# Externals.net
KiCad netlist of a schematic drawn in Altium Designer
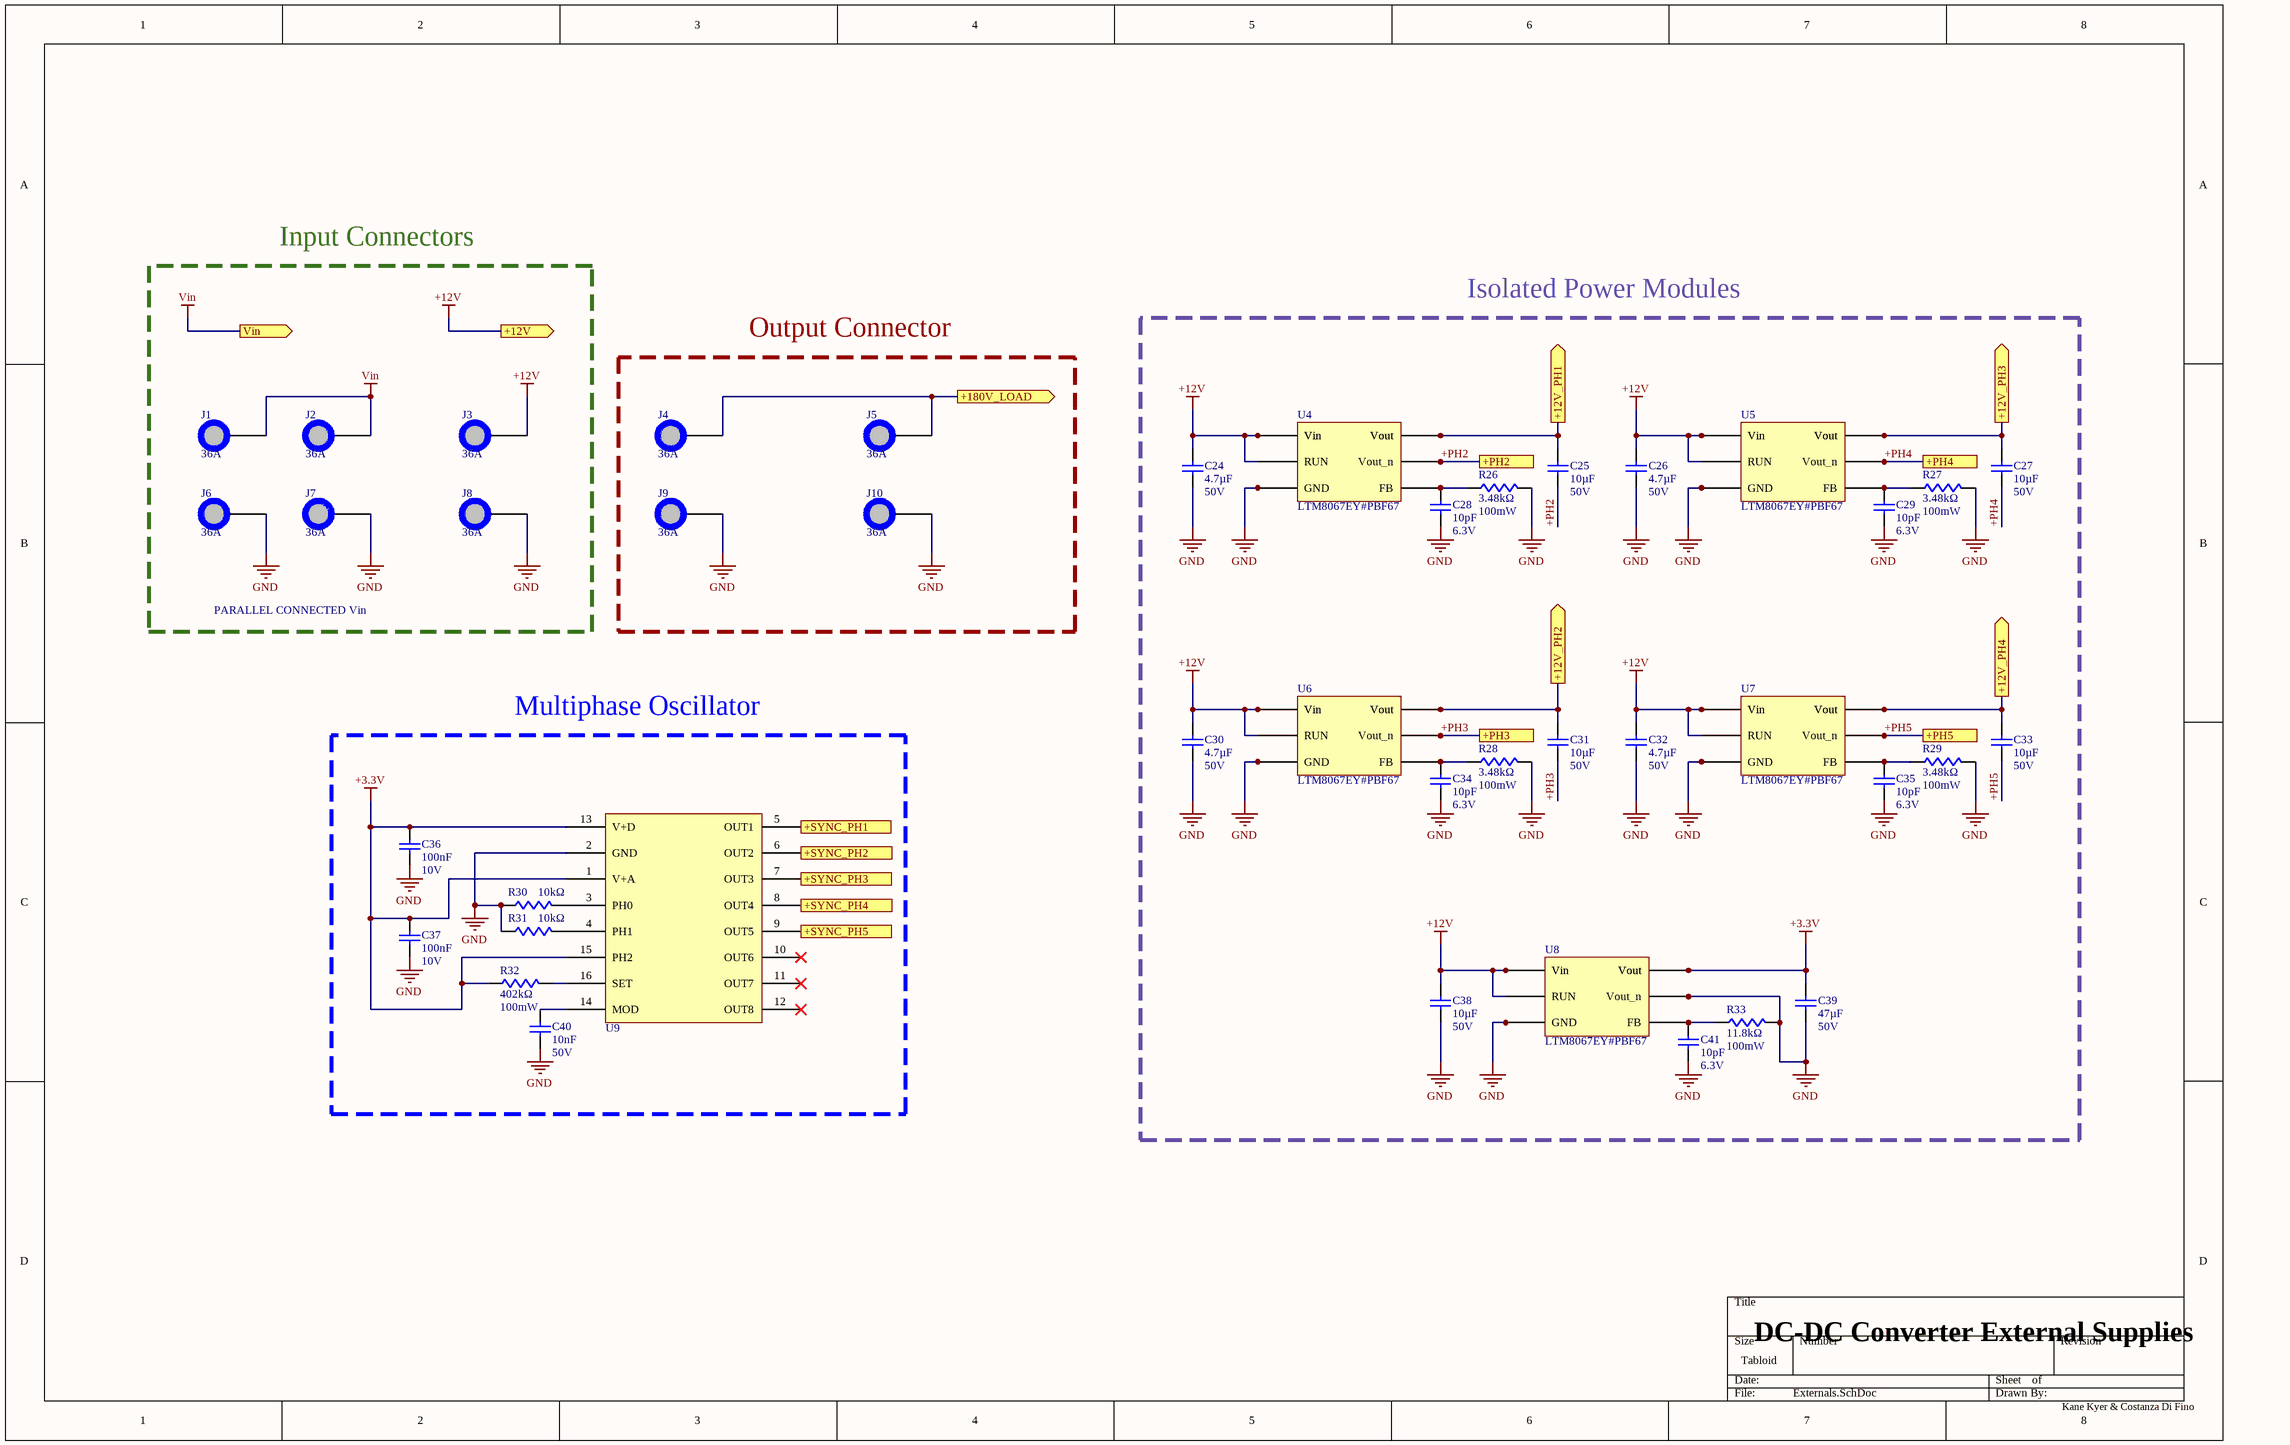
[diagram p0: Externals.SchDoc]

(export (version "E")
  (design (tool "Eeschema 10.0.6"))
  (components
    (comp (ref "C24")
      (value "4.7µF")
      (footprint "C_1206")
      (fields
        (field (name "MANUFACTURER") "Cal-Chip Electronics")
        (field (name "MANUFACTURER PART NUMBER") "GMC31X7R475K50NT")
        (field (name "VOLTAGE RATING (DC)") "50V")
      )
      (libsource (lib "library") (part "GMC31X7R475K50NT"))
    )
    (comp (ref "C25")
      (value "10µF")
      (footprint "C_1206")
      (description "50V 10uF X7R ±10% 1206 Multilayer Ceramic Capacitors MLCC - SMD/SMT ROHS")
      (fields
        (field (name "MANUFACTURER") "Samsung Electro-Mechanics")
        (field (name "MANUFACTURER PART NUMBER") "CL31B106KBHNNNE")
        (field (name "VOLTAGE RATING") "50V")
      )
      (libsource (lib "library") (part "CL31B106KBHNNNE"))
    )
    (comp (ref "C26")
      (value "4.7µF")
      (footprint "C_1206")
      (fields
        (field (name "MANUFACTURER") "Cal-Chip Electronics")
        (field (name "MANUFACTURER PART NUMBER") "GMC31X7R475K50NT")
        (field (name "VOLTAGE RATING (DC)") "50V")
      )
      (libsource (lib "library") (part "GMC31X7R475K50NT"))
    )
    (comp (ref "C27")
      (value "10µF")
      (footprint "C_1206")
      (description "50V 10uF X7R ±10% 1206 Multilayer Ceramic Capacitors MLCC - SMD/SMT ROHS")
      (fields
        (field (name "MANUFACTURER") "Samsung Electro-Mechanics")
        (field (name "MANUFACTURER PART NUMBER") "CL31B106KBHNNNE")
        (field (name "VOLTAGE RATING") "50V")
      )
      (libsource (lib "library") (part "CL31B106KBHNNNE"))
    )
    (comp (ref "C28")
      (value "10pF")
      (footprint "C_0402")
      (description "0402 10 pF 6.3 V ±10 % Tolerance C0G/NP0 SMT Multilayer Ceramic Capacitor")
      (fields
        (field (name "MANUFACTURER") "KYOCERA AVX")
        (field (name "MANUFACTURER PART NUMBER") "04026A100KAT2A")
        (field (name "VOLTAGE RATING") "6.3V")
      )
      (libsource (lib "library") (part "04026A100KAT2A"))
    )
    (comp (ref "C29")
      (value "10pF")
      (footprint "C_0402")
      (description "0402 10 pF 6.3 V ±10 % Tolerance C0G/NP0 SMT Multilayer Ceramic Capacitor")
      (fields
        (field (name "MANUFACTURER") "KYOCERA AVX")
        (field (name "MANUFACTURER PART NUMBER") "04026A100KAT2A")
        (field (name "VOLTAGE RATING") "6.3V")
      )
      (libsource (lib "library") (part "04026A100KAT2A"))
    )
    (comp (ref "C30")
      (value "4.7µF")
      (footprint "C_1206")
      (fields
        (field (name "MANUFACTURER") "Cal-Chip Electronics")
        (field (name "MANUFACTURER PART NUMBER") "GMC31X7R475K50NT")
        (field (name "VOLTAGE RATING (DC)") "50V")
      )
      (libsource (lib "library") (part "GMC31X7R475K50NT"))
    )
    (comp (ref "C31")
      (value "10µF")
      (footprint "C_1206")
      (description "50V 10uF X7R ±10% 1206 Multilayer Ceramic Capacitors MLCC - SMD/SMT ROHS")
      (fields
        (field (name "MANUFACTURER") "Samsung Electro-Mechanics")
        (field (name "MANUFACTURER PART NUMBER") "CL31B106KBHNNNE")
        (field (name "VOLTAGE RATING") "50V")
      )
      (libsource (lib "library") (part "CL31B106KBHNNNE"))
    )
    (comp (ref "C32")
      (value "4.7µF")
      (footprint "C_1206")
      (fields
        (field (name "MANUFACTURER") "Cal-Chip Electronics")
        (field (name "MANUFACTURER PART NUMBER") "GMC31X7R475K50NT")
        (field (name "VOLTAGE RATING (DC)") "50V")
      )
      (libsource (lib "library") (part "GMC31X7R475K50NT"))
    )
    (comp (ref "C33")
      (value "10µF")
      (footprint "C_1206")
      (description "50V 10uF X7R ±10% 1206 Multilayer Ceramic Capacitors MLCC - SMD/SMT ROHS")
      (fields
        (field (name "MANUFACTURER") "Samsung Electro-Mechanics")
        (field (name "MANUFACTURER PART NUMBER") "CL31B106KBHNNNE")
        (field (name "VOLTAGE RATING") "50V")
      )
      (libsource (lib "library") (part "CL31B106KBHNNNE"))
    )
    (comp (ref "C34")
      (value "10pF")
      (footprint "C_0402")
      (description "0402 10 pF 6.3 V ±10 % Tolerance C0G/NP0 SMT Multilayer Ceramic Capacitor")
      (fields
        (field (name "MANUFACTURER") "KYOCERA AVX")
        (field (name "MANUFACTURER PART NUMBER") "04026A100KAT2A")
        (field (name "VOLTAGE RATING") "6.3V")
      )
      (libsource (lib "library") (part "04026A100KAT2A"))
    )
    (comp (ref "C35")
      (value "10pF")
      (footprint "C_0402")
      (description "0402 10 pF 6.3 V ±10 % Tolerance C0G/NP0 SMT Multilayer Ceramic Capacitor")
      (fields
        (field (name "MANUFACTURER") "KYOCERA AVX")
        (field (name "MANUFACTURER PART NUMBER") "04026A100KAT2A")
        (field (name "VOLTAGE RATING") "6.3V")
      )
      (libsource (lib "library") (part "04026A100KAT2A"))
    )
    (comp (ref "C36")
      (value "100nF")
      (footprint "C_0402")
      (description "10V 100nF X7R ±10% 0402 Multilayer Ceramic Capacitors MLCC - SMD/SMT ROHS")
      (fields
        (field (name "MANUFACTURER") "Cal-Chip Electronics")
        (field (name "MANUFACTURER PART NUMBER") "GMC04X7R104K10NT")
        (field (name "VOLTAGE RATING (DC)") "10V")
      )
      (libsource (lib "library") (part "GMC04X7R104K10NT"))
    )
    (comp (ref "C37")
      (value "100nF")
      (footprint "C_0402")
      (description "10V 100nF X7R ±10% 0402 Multilayer Ceramic Capacitors MLCC - SMD/SMT ROHS")
      (fields
        (field (name "MANUFACTURER") "Cal-Chip Electronics")
        (field (name "MANUFACTURER PART NUMBER") "GMC04X7R104K10NT")
        (field (name "VOLTAGE RATING (DC)") "10V")
      )
      (libsource (lib "library") (part "GMC04X7R104K10NT"))
    )
    (comp (ref "C38")
      (value "10µF")
      (footprint "C_1206")
      (description "50V 10uF X7R ±10% 1206 Multilayer Ceramic Capacitors MLCC - SMD/SMT ROHS")
      (fields
        (field (name "MANUFACTURER") "Samsung Electro-Mechanics")
        (field (name "MANUFACTURER PART NUMBER") "CL31B106KBHNNNE")
        (field (name "VOLTAGE RATING") "50V")
      )
      (libsource (lib "library") (part "CL31B106KBHNNNE"))
    )
    (comp (ref "C39")
      (value "47µF")
      (footprint "C_CKG57N")
      (fields
        (field (name "MANUFACTURER") "TDK")
        (field (name "MANUFACTURER PART NUMBER") "CKG57NX7R1H476M500JJ")
        (field (name "VOLTAGE RATING (DC)") "50V")
      )
      (libsource (lib "library") (part "CKG57NX7R1H476M500JJ"))
    )
    (comp (ref "C40")
      (value "10nF")
      (footprint "C_0603")
      (description "Capacitor, Multilayer, Ceramic, 50V, 10%, X7R, 15% Tc, 0.01Uf, Surface Mount, 0603")
      (fields
        (field (name "MANUFACTURER") "KEMET")
        (field (name "MANUFACTURER PART NUMBER") "C0603C103K5RACTU")
        (field (name "VOLTAGE RATING") "50V")
      )
      (libsource (lib "library") (part "C0603C103K5RACTU"))
    )
    (comp (ref "C41")
      (value "10pF")
      (footprint "C_0402")
      (description "0402 10 pF 6.3 V ±10 % Tolerance C0G/NP0 SMT Multilayer Ceramic Capacitor")
      (fields
        (field (name "MANUFACTURER") "KYOCERA AVX")
        (field (name "MANUFACTURER PART NUMBER") "04026A100KAT2A")
        (field (name "VOLTAGE RATING") "6.3V")
      )
      (libsource (lib "library") (part "04026A100KAT2A"))
    )
    (comp (ref "J1")
      (value "SMTSO-116-8ET")
      (footprint "PEM")
      (description "ReelFast Surface Mount Nuts and Spacers/Standoffs -br Type SMTSO - Unified")
      (fields (field (name "MANUFACTURER") "PennEngineering") (field (name "CURRENT RATING") "36A"))
      (libsource (lib "library") (part "SMTSO-116-8ET"))
    )
    (comp (ref "J2")
      (value "SMTSO-116-8ET")
      (footprint "PEM")
      (description "ReelFast Surface Mount Nuts and Spacers/Standoffs -br Type SMTSO - Unified")
      (fields (field (name "MANUFACTURER") "PennEngineering") (field (name "CURRENT RATING") "36A"))
      (libsource (lib "library") (part "SMTSO-116-8ET"))
    )
    (comp (ref "J3")
      (value "SMTSO-116-8ET")
      (footprint "PEM")
      (description "ReelFast Surface Mount Nuts and Spacers/Standoffs -br Type SMTSO - Unified")
      (fields (field (name "MANUFACTURER") "PennEngineering") (field (name "CURRENT RATING") "36A"))
      (libsource (lib "library") (part "SMTSO-116-8ET"))
    )
    (comp (ref "J4")
      (value "SMTSO-116-8ET")
      (footprint "PEM")
      (description "ReelFast Surface Mount Nuts and Spacers/Standoffs -br Type SMTSO - Unified")
      (fields (field (name "MANUFACTURER") "PennEngineering") (field (name "CURRENT RATING") "36A"))
      (libsource (lib "library") (part "SMTSO-116-8ET"))
    )
    (comp (ref "J5")
      (value "SMTSO-116-8ET")
      (footprint "PEM")
      (description "ReelFast Surface Mount Nuts and Spacers/Standoffs -br Type SMTSO - Unified")
      (fields (field (name "MANUFACTURER") "PennEngineering") (field (name "CURRENT RATING") "36A"))
      (libsource (lib "library") (part "SMTSO-116-8ET"))
    )
    (comp (ref "J6")
      (value "SMTSO-116-8ET")
      (footprint "PEM")
      (description "ReelFast Surface Mount Nuts and Spacers/Standoffs -br Type SMTSO - Unified")
      (fields (field (name "MANUFACTURER") "PennEngineering") (field (name "CURRENT RATING") "36A"))
      (libsource (lib "library") (part "SMTSO-116-8ET"))
    )
    (comp (ref "J7")
      (value "SMTSO-116-8ET")
      (footprint "PEM")
      (description "ReelFast Surface Mount Nuts and Spacers/Standoffs -br Type SMTSO - Unified")
      (fields (field (name "MANUFACTURER") "PennEngineering") (field (name "CURRENT RATING") "36A"))
      (libsource (lib "library") (part "SMTSO-116-8ET"))
    )
    (comp (ref "J8")
      (value "SMTSO-116-8ET")
      (footprint "PEM")
      (description "ReelFast Surface Mount Nuts and Spacers/Standoffs -br Type SMTSO - Unified")
      (fields (field (name "MANUFACTURER") "PennEngineering") (field (name "CURRENT RATING") "36A"))
      (libsource (lib "library") (part "SMTSO-116-8ET"))
    )
    (comp (ref "J9")
      (value "SMTSO-116-8ET")
      (footprint "PEM")
      (description "ReelFast Surface Mount Nuts and Spacers/Standoffs -br Type SMTSO - Unified")
      (fields (field (name "MANUFACTURER") "PennEngineering") (field (name "CURRENT RATING") "36A"))
      (libsource (lib "library") (part "SMTSO-116-8ET"))
    )
    (comp (ref "J10")
      (value "SMTSO-116-8ET")
      (footprint "PEM")
      (description "ReelFast Surface Mount Nuts and Spacers/Standoffs -br Type SMTSO - Unified")
      (fields (field (name "MANUFACTURER") "PennEngineering") (field (name "CURRENT RATING") "36A"))
      (libsource (lib "library") (part "SMTSO-116-8ET"))
    )
    (comp (ref "R26")
      (value "3.48kΩ")
      (footprint "R_0603")
      (description "Fixed Resistor, Metal Glaze/thick Film, 0.1W, 3480ohm, 75V, 1% +/-Tol, Surface Mount, 0603")
      (fields
        (field (name "MANUFACTURER") "Cal-Chip Electronics")
        (field (name "MANUFACTURER PART NUMBER") "RM06F3481CT")
        (field (name "POWER DISSIPATION") "100mW")
      )
      (libsource (lib "library") (part "RM06F3481CT"))
    )
    (comp (ref "R27")
      (value "3.48kΩ")
      (footprint "R_0603")
      (description "Fixed Resistor, Metal Glaze/thick Film, 0.1W, 3480ohm, 75V, 1% +/-Tol, Surface Mount, 0603")
      (fields
        (field (name "MANUFACTURER") "Cal-Chip Electronics")
        (field (name "MANUFACTURER PART NUMBER") "RM06F3481CT")
        (field (name "POWER DISSIPATION") "100mW")
      )
      (libsource (lib "library") (part "RM06F3481CT"))
    )
    (comp (ref "R28")
      (value "3.48kΩ")
      (footprint "R_0603")
      (description "Fixed Resistor, Metal Glaze/thick Film, 0.1W, 3480ohm, 75V, 1% +/-Tol, Surface Mount, 0603")
      (fields
        (field (name "MANUFACTURER") "Cal-Chip Electronics")
        (field (name "MANUFACTURER PART NUMBER") "RM06F3481CT")
        (field (name "POWER DISSIPATION") "100mW")
      )
      (libsource (lib "library") (part "RM06F3481CT"))
    )
    (comp (ref "R29")
      (value "3.48kΩ")
      (footprint "R_0603")
      (description "Fixed Resistor, Metal Glaze/thick Film, 0.1W, 3480ohm, 75V, 1% +/-Tol, Surface Mount, 0603")
      (fields
        (field (name "MANUFACTURER") "Cal-Chip Electronics")
        (field (name "MANUFACTURER PART NUMBER") "RM06F3481CT")
        (field (name "POWER DISSIPATION") "100mW")
      )
      (libsource (lib "library") (part "RM06F3481CT"))
    )
    (comp (ref "R30")
      (value "10kΩ")
      (footprint "R_0402")
      (description "Fixed Resistor, Metal Glaze/thick Film, 0.0625W, 10000ohm, 50V, 1% +/-Tol, Surface Mount, 0402")
      (fields
        (field (name "MANUFACTURER") "Cal-Chip Electronics")
        (field (name "MANUFACTURER PART NUMBER") "RM04F1002CT")
      )
      (libsource (lib "library") (part "RM04F1002CT"))
    )
    (comp (ref "R31")
      (value "10kΩ")
      (footprint "R_0402")
      (description "Fixed Resistor, Metal Glaze/thick Film, 0.0625W, 10000ohm, 50V, 1% +/-Tol, Surface Mount, 0402")
      (fields
        (field (name "MANUFACTURER") "Cal-Chip Electronics")
        (field (name "MANUFACTURER PART NUMBER") "RM04F1002CT")
      )
      (libsource (lib "library") (part "RM04F1002CT"))
    )
    (comp (ref "R32")
      (value "402kΩ")
      (footprint "R_0603")
      (description "100mW Thick Film Resistors 75V ±100ppm/℃ ±1% 402kΩ 0603 Chip Resistor - Surface Mount ROHS")
      (fields
        (field (name "MANUFACTURER") "Yageo Group")
        (field (name "MANUFACTURER PART NUMBER") "RC0603FR-07402KL")
        (field (name "POWER DISSIPATION") "100mW")
      )
      (libsource (lib "library") (part "RC0603FR-07402KL"))
    )
    (comp (ref "R33")
      (value "11.8kΩ")
      (footprint "R_0603")
      (description "Res Thick Film 0603 11.8K Ohm 1% 0.1W(1/10W) ±100ppm/C Pad SMD Automotive T/R")
      (fields
        (field (name "MANUFACTURER") "KOA Speer")
        (field (name "MANUFACTURER PART NUMBER") "RK73H1JTTD1182F")
        (field (name "POWER DISSIPATION") "100mW")
      )
      (libsource (lib "library") (part "RK73H1JTTD1182F"))
    )
    (comp (ref "U4")
      (value "LTM8067EY#PBF")
      (footprint "LTM8067")
      (description "Module DC-DC 1-OUT 2.5V to 24V 0.45A 2.5W 38-Pin BGA Tray")
      (fields
        (field (name "MANUFACTURER") "Analog Devices")
        (field (name "MANUFACTURER PART NUMBER") "LTM8067EY#PBF67")
      )
      (libsource (lib "library") (part "LTM8067EY#PBF"))
    )
    (comp (ref "U5")
      (value "LTM8067EY#PBF")
      (footprint "LTM8067")
      (description "Module DC-DC 1-OUT 2.5V to 24V 0.45A 2.5W 38-Pin BGA Tray")
      (fields
        (field (name "MANUFACTURER") "Analog Devices")
        (field (name "MANUFACTURER PART NUMBER") "LTM8067EY#PBF67")
      )
      (libsource (lib "library") (part "LTM8067EY#PBF"))
    )
    (comp (ref "U6")
      (value "LTM8067EY#PBF")
      (footprint "LTM8067")
      (description "Module DC-DC 1-OUT 2.5V to 24V 0.45A 2.5W 38-Pin BGA Tray")
      (fields
        (field (name "MANUFACTURER") "Analog Devices")
        (field (name "MANUFACTURER PART NUMBER") "LTM8067EY#PBF67")
      )
      (libsource (lib "library") (part "LTM8067EY#PBF"))
    )
    (comp (ref "U7")
      (value "LTM8067EY#PBF")
      (footprint "LTM8067")
      (description "Module DC-DC 1-OUT 2.5V to 24V 0.45A 2.5W 38-Pin BGA Tray")
      (fields
        (field (name "MANUFACTURER") "Analog Devices")
        (field (name "MANUFACTURER PART NUMBER") "LTM8067EY#PBF67")
      )
      (libsource (lib "library") (part "LTM8067EY#PBF"))
    )
    (comp (ref "U8")
      (value "LTM8067EY#PBF")
      (footprint "LTM8067")
      (description "Module DC-DC 1-OUT 2.5V to 24V 0.45A 2.5W 38-Pin BGA Tray")
      (fields
        (field (name "MANUFACTURER") "Analog Devices")
        (field (name "MANUFACTURER PART NUMBER") "LTM8067EY#PBF67")
      )
      (libsource (lib "library") (part "LTM8067EY#PBF"))
    )
    (comp (ref "U9")
      (value "LTC6909HMS#TRPBF")
      (footprint "LTC6909")
      (description "1 to 8 Output, Multiphase Silicon Oscillator with Spread Spectrum Modulation")
      (fields (field (name "MANUFACTURER") "Analog Devices"))
      (libsource (lib "library") (part "LTC6909HMS#TRPBF"))
    )
  )
  (nets
    (net (code "1") (name "+3.3V") (class "Default")
      (node (ref "C36") (pin "2") (pintype "passive"))
      (node (ref "C37") (pin "2") (pintype "passive"))
      (node (ref "C39") (pin "2") (pintype "passive"))
      (node (ref "R32") (pin "1") (pintype "passive"))
      (node (ref "U8") (pin "A6") (pinfunction "Vout_A6") (pintype "passive"))
      (node (ref "U8") (pin "A7") (pinfunction "Vout_A7") (pintype "passive"))
      (node (ref "U8") (pin "B6") (pinfunction "Vout_B6") (pintype "passive"))
      (node (ref "U8") (pin "B7") (pinfunction "Vout_B7") (pintype "passive"))
      (node (ref "U9") (pin "1") (pinfunction "V+A_1") (pintype "passive"))
      (node (ref "U9") (pin "13") (pinfunction "V+D_13") (pintype "passive"))
      (node (ref "U9") (pin "15") (pinfunction "PH2_15") (pintype "passive"))
    )
    (net (code "2") (name "+12V") (class "Default")
      (node (ref "C24") (pin "2") (pintype "passive"))
      (node (ref "C26") (pin "2") (pintype "passive"))
      (node (ref "C30") (pin "2") (pintype "passive"))
      (node (ref "C32") (pin "2") (pintype "passive"))
      (node (ref "C38") (pin "2") (pintype "passive"))
      (node (ref "J3") (pin "1") (pinfunction "1_1") (pintype "passive"))
      (node (ref "U4") (pin "F3") (pinfunction "RUN_F3") (pintype "passive"))
      (node (ref "U4") (pin "G1") (pinfunction "Vin_G1") (pintype "passive"))
      (node (ref "U4") (pin "G2") (pinfunction "Vin_G2") (pintype "passive"))
      (node (ref "U4") (pin "H1") (pinfunction "Vin_H1") (pintype "passive"))
      (node (ref "U4") (pin "H2") (pinfunction "Vin_H2") (pintype "passive"))
      (node (ref "U5") (pin "F3") (pinfunction "RUN_F3") (pintype "passive"))
      (node (ref "U5") (pin "G1") (pinfunction "Vin_G1") (pintype "passive"))
      (node (ref "U5") (pin "G2") (pinfunction "Vin_G2") (pintype "passive"))
      (node (ref "U5") (pin "H1") (pinfunction "Vin_H1") (pintype "passive"))
      (node (ref "U5") (pin "H2") (pinfunction "Vin_H2") (pintype "passive"))
      (node (ref "U6") (pin "F3") (pinfunction "RUN_F3") (pintype "passive"))
      (node (ref "U6") (pin "G1") (pinfunction "Vin_G1") (pintype "passive"))
      (node (ref "U6") (pin "G2") (pinfunction "Vin_G2") (pintype "passive"))
      (node (ref "U6") (pin "H1") (pinfunction "Vin_H1") (pintype "passive"))
      (node (ref "U6") (pin "H2") (pinfunction "Vin_H2") (pintype "passive"))
      (node (ref "U7") (pin "F3") (pinfunction "RUN_F3") (pintype "passive"))
      (node (ref "U7") (pin "G1") (pinfunction "Vin_G1") (pintype "passive"))
      (node (ref "U7") (pin "G2") (pinfunction "Vin_G2") (pintype "passive"))
      (node (ref "U7") (pin "H1") (pinfunction "Vin_H1") (pintype "passive"))
      (node (ref "U7") (pin "H2") (pinfunction "Vin_H2") (pintype "passive"))
      (node (ref "U8") (pin "F3") (pinfunction "RUN_F3") (pintype "passive"))
      (node (ref "U8") (pin "G1") (pinfunction "Vin_G1") (pintype "passive"))
      (node (ref "U8") (pin "G2") (pinfunction "Vin_G2") (pintype "passive"))
      (node (ref "U8") (pin "H1") (pinfunction "Vin_H1") (pintype "passive"))
      (node (ref "U8") (pin "H2") (pinfunction "Vin_H2") (pintype "passive"))
    )
    (net (code "3") (name "/+12V_PH1") (class "Default")
      (node (ref "C25") (pin "2") (pintype "passive"))
      (node (ref "U4") (pin "A6") (pinfunction "Vout_A6") (pintype "passive"))
      (node (ref "U4") (pin "A7") (pinfunction "Vout_A7") (pintype "passive"))
      (node (ref "U4") (pin "B6") (pinfunction "Vout_B6") (pintype "passive"))
      (node (ref "U4") (pin "B7") (pinfunction "Vout_B7") (pintype "passive"))
    )
    (net (code "4") (name "/+12V_PH2") (class "Default")
      (node (ref "C31") (pin "2") (pintype "passive"))
      (node (ref "U6") (pin "A6") (pinfunction "Vout_A6") (pintype "passive"))
      (node (ref "U6") (pin "A7") (pinfunction "Vout_A7") (pintype "passive"))
      (node (ref "U6") (pin "B6") (pinfunction "Vout_B6") (pintype "passive"))
      (node (ref "U6") (pin "B7") (pinfunction "Vout_B7") (pintype "passive"))
    )
    (net (code "5") (name "/+12V_PH3") (class "Default")
      (node (ref "C27") (pin "2") (pintype "passive"))
      (node (ref "U5") (pin "A6") (pinfunction "Vout_A6") (pintype "passive"))
      (node (ref "U5") (pin "A7") (pinfunction "Vout_A7") (pintype "passive"))
      (node (ref "U5") (pin "B6") (pinfunction "Vout_B6") (pintype "passive"))
      (node (ref "U5") (pin "B7") (pinfunction "Vout_B7") (pintype "passive"))
    )
    (net (code "6") (name "/+12V_PH4") (class "Default")
      (node (ref "C33") (pin "2") (pintype "passive"))
      (node (ref "U7") (pin "A6") (pinfunction "Vout_A6") (pintype "passive"))
      (node (ref "U7") (pin "A7") (pinfunction "Vout_A7") (pintype "passive"))
      (node (ref "U7") (pin "B6") (pinfunction "Vout_B6") (pintype "passive"))
      (node (ref "U7") (pin "B7") (pinfunction "Vout_B7") (pintype "passive"))
    )
    (net (code "7") (name "/+180V_LOAD") (class "Default")
      (node (ref "J4") (pin "1") (pinfunction "1_1") (pintype "passive"))
      (node (ref "J5") (pin "1") (pinfunction "1_1") (pintype "passive"))
    )
    (net (code "8") (name "/+PH2") (class "Default")
      (node (ref "C25") (pin "1") (pintype "passive"))
      (node (ref "U4") (pin "A1") (pinfunction "Vout_n_A1") (pintype "passive"))
      (node (ref "U4") (pin "A2") (pinfunction "Vout_n_A2") (pintype "passive"))
      (node (ref "U4") (pin "A3") (pinfunction "Vout_n_A3") (pintype "passive"))
      (node (ref "U4") (pin "A4") (pinfunction "Vout_n_A4") (pintype "passive"))
      (node (ref "U4") (pin "A5") (pinfunction "Vout_n_A5") (pintype "passive"))
      (node (ref "U4") (pin "B1") (pinfunction "Vout_n_B1") (pintype "passive"))
      (node (ref "U4") (pin "B2") (pinfunction "Vout_n_B2") (pintype "passive"))
      (node (ref "U4") (pin "B3") (pinfunction "Vout_n_B3") (pintype "passive"))
      (node (ref "U4") (pin "B4") (pinfunction "Vout_n_B4") (pintype "passive"))
      (node (ref "U4") (pin "B5") (pinfunction "Vout_n_B5") (pintype "passive"))
    )
    (net (code "9") (name "/+PH3") (class "Default")
      (node (ref "C31") (pin "1") (pintype "passive"))
      (node (ref "U6") (pin "A1") (pinfunction "Vout_n_A1") (pintype "passive"))
      (node (ref "U6") (pin "A2") (pinfunction "Vout_n_A2") (pintype "passive"))
      (node (ref "U6") (pin "A3") (pinfunction "Vout_n_A3") (pintype "passive"))
      (node (ref "U6") (pin "A4") (pinfunction "Vout_n_A4") (pintype "passive"))
      (node (ref "U6") (pin "A5") (pinfunction "Vout_n_A5") (pintype "passive"))
      (node (ref "U6") (pin "B1") (pinfunction "Vout_n_B1") (pintype "passive"))
      (node (ref "U6") (pin "B2") (pinfunction "Vout_n_B2") (pintype "passive"))
      (node (ref "U6") (pin "B3") (pinfunction "Vout_n_B3") (pintype "passive"))
      (node (ref "U6") (pin "B4") (pinfunction "Vout_n_B4") (pintype "passive"))
      (node (ref "U6") (pin "B5") (pinfunction "Vout_n_B5") (pintype "passive"))
    )
    (net (code "10") (name "/+PH4") (class "Default")
      (node (ref "C27") (pin "1") (pintype "passive"))
      (node (ref "U5") (pin "A1") (pinfunction "Vout_n_A1") (pintype "passive"))
      (node (ref "U5") (pin "A2") (pinfunction "Vout_n_A2") (pintype "passive"))
      (node (ref "U5") (pin "A3") (pinfunction "Vout_n_A3") (pintype "passive"))
      (node (ref "U5") (pin "A4") (pinfunction "Vout_n_A4") (pintype "passive"))
      (node (ref "U5") (pin "A5") (pinfunction "Vout_n_A5") (pintype "passive"))
      (node (ref "U5") (pin "B1") (pinfunction "Vout_n_B1") (pintype "passive"))
      (node (ref "U5") (pin "B2") (pinfunction "Vout_n_B2") (pintype "passive"))
      (node (ref "U5") (pin "B3") (pinfunction "Vout_n_B3") (pintype "passive"))
      (node (ref "U5") (pin "B4") (pinfunction "Vout_n_B4") (pintype "passive"))
      (node (ref "U5") (pin "B5") (pinfunction "Vout_n_B5") (pintype "passive"))
    )
    (net (code "11") (name "/+PH5") (class "Default")
      (node (ref "C33") (pin "1") (pintype "passive"))
      (node (ref "U7") (pin "A1") (pinfunction "Vout_n_A1") (pintype "passive"))
      (node (ref "U7") (pin "A2") (pinfunction "Vout_n_A2") (pintype "passive"))
      (node (ref "U7") (pin "A3") (pinfunction "Vout_n_A3") (pintype "passive"))
      (node (ref "U7") (pin "A4") (pinfunction "Vout_n_A4") (pintype "passive"))
      (node (ref "U7") (pin "A5") (pinfunction "Vout_n_A5") (pintype "passive"))
      (node (ref "U7") (pin "B1") (pinfunction "Vout_n_B1") (pintype "passive"))
      (node (ref "U7") (pin "B2") (pinfunction "Vout_n_B2") (pintype "passive"))
      (node (ref "U7") (pin "B3") (pinfunction "Vout_n_B3") (pintype "passive"))
      (node (ref "U7") (pin "B4") (pinfunction "Vout_n_B4") (pintype "passive"))
      (node (ref "U7") (pin "B5") (pinfunction "Vout_n_B5") (pintype "passive"))
    )
    (net (code "12") (name "/+SYNC_PH1") (class "Default")
      (node (ref "U9") (pin "5") (pinfunction "OUT1_5") (pintype "passive"))
    )
    (net (code "13") (name "/+SYNC_PH2") (class "Default")
      (node (ref "U9") (pin "6") (pinfunction "OUT2_6") (pintype "passive"))
    )
    (net (code "14") (name "/+SYNC_PH3") (class "Default")
      (node (ref "U9") (pin "7") (pinfunction "OUT3_7") (pintype "passive"))
    )
    (net (code "15") (name "/+SYNC_PH4") (class "Default")
      (node (ref "U9") (pin "8") (pinfunction "OUT4_8") (pintype "passive"))
    )
    (net (code "16") (name "/+SYNC_PH5") (class "Default")
      (node (ref "U9") (pin "9") (pinfunction "OUT5_9") (pintype "passive"))
    )
    (net (code "17") (name "GND") (class "Default")
      (node (ref "C24") (pin "1") (pintype "passive"))
      (node (ref "C26") (pin "1") (pintype "passive"))
      (node (ref "C28") (pin "2") (pintype "passive"))
      (node (ref "C29") (pin "2") (pintype "passive"))
      (node (ref "C30") (pin "1") (pintype "passive"))
      (node (ref "C32") (pin "1") (pintype "passive"))
      (node (ref "C34") (pin "2") (pintype "passive"))
      (node (ref "C35") (pin "2") (pintype "passive"))
      (node (ref "C36") (pin "1") (pintype "passive"))
      (node (ref "C37") (pin "1") (pintype "passive"))
      (node (ref "C38") (pin "1") (pintype "passive"))
      (node (ref "C39") (pin "1") (pintype "passive"))
      (node (ref "C40") (pin "1") (pintype "passive"))
      (node (ref "C41") (pin "2") (pintype "passive"))
      (node (ref "J10") (pin "1") (pinfunction "1_1") (pintype "passive"))
      (node (ref "J6") (pin "1") (pinfunction "1_1") (pintype "passive"))
      (node (ref "J7") (pin "1") (pinfunction "1_1") (pintype "passive"))
      (node (ref "J8") (pin "1") (pinfunction "1_1") (pintype "passive"))
      (node (ref "J9") (pin "1") (pinfunction "1_1") (pintype "passive"))
      (node (ref "R26") (pin "2") (pintype "passive"))
      (node (ref "R27") (pin "2") (pintype "passive"))
      (node (ref "R28") (pin "2") (pintype "passive"))
      (node (ref "R29") (pin "2") (pintype "passive"))
      (node (ref "R30") (pin "1") (pintype "passive"))
      (node (ref "R31") (pin "1") (pintype "passive"))
      (node (ref "R33") (pin "2") (pintype "passive"))
      (node (ref "U4") (pin "E1") (pinfunction "GND_E1") (pintype "passive"))
      (node (ref "U4") (pin "E2") (pinfunction "GND_E2") (pintype "passive"))
      (node (ref "U4") (pin "E3") (pinfunction "GND_E3") (pintype "passive"))
      (node (ref "U4") (pin "E4") (pinfunction "GND_E4") (pintype "passive"))
      (node (ref "U4") (pin "E5") (pinfunction "GND_E5") (pintype "passive"))
      (node (ref "U4") (pin "E6") (pinfunction "GND_E6") (pintype "passive"))
      (node (ref "U4") (pin "E7") (pinfunction "GND_E7") (pintype "passive"))
      (node (ref "U4") (pin "F4") (pinfunction "GND_F4") (pintype "passive"))
      (node (ref "U4") (pin "F5") (pinfunction "GND_F5") (pintype "passive"))
      (node (ref "U4") (pin "F6") (pinfunction "GND_F6") (pintype "passive"))
      (node (ref "U4") (pin "F7") (pinfunction "GND_F7") (pintype "passive"))
      (node (ref "U4") (pin "G4") (pinfunction "GND_G4") (pintype "passive"))
      (node (ref "U4") (pin "G5") (pinfunction "GND_G5") (pintype "passive"))
      (node (ref "U4") (pin "G6") (pinfunction "GND_G6") (pintype "passive"))
      (node (ref "U4") (pin "H4") (pinfunction "GND_H4") (pintype "passive"))
      (node (ref "U4") (pin "H5") (pinfunction "GND_H5") (pintype "passive"))
      (node (ref "U4") (pin "H6") (pinfunction "GND_H6") (pintype "passive"))
      (node (ref "U4") (pin "H7") (pinfunction "GND_H7") (pintype "passive"))
      (node (ref "U5") (pin "E1") (pinfunction "GND_E1") (pintype "passive"))
      (node (ref "U5") (pin "E2") (pinfunction "GND_E2") (pintype "passive"))
      (node (ref "U5") (pin "E3") (pinfunction "GND_E3") (pintype "passive"))
      (node (ref "U5") (pin "E4") (pinfunction "GND_E4") (pintype "passive"))
      (node (ref "U5") (pin "E5") (pinfunction "GND_E5") (pintype "passive"))
      (node (ref "U5") (pin "E6") (pinfunction "GND_E6") (pintype "passive"))
      (node (ref "U5") (pin "E7") (pinfunction "GND_E7") (pintype "passive"))
      (node (ref "U5") (pin "F4") (pinfunction "GND_F4") (pintype "passive"))
      (node (ref "U5") (pin "F5") (pinfunction "GND_F5") (pintype "passive"))
      (node (ref "U5") (pin "F6") (pinfunction "GND_F6") (pintype "passive"))
      (node (ref "U5") (pin "F7") (pinfunction "GND_F7") (pintype "passive"))
      (node (ref "U5") (pin "G4") (pinfunction "GND_G4") (pintype "passive"))
      (node (ref "U5") (pin "G5") (pinfunction "GND_G5") (pintype "passive"))
      (node (ref "U5") (pin "G6") (pinfunction "GND_G6") (pintype "passive"))
      (node (ref "U5") (pin "H4") (pinfunction "GND_H4") (pintype "passive"))
      (node (ref "U5") (pin "H5") (pinfunction "GND_H5") (pintype "passive"))
      (node (ref "U5") (pin "H6") (pinfunction "GND_H6") (pintype "passive"))
      (node (ref "U5") (pin "H7") (pinfunction "GND_H7") (pintype "passive"))
      (node (ref "U6") (pin "E1") (pinfunction "GND_E1") (pintype "passive"))
      (node (ref "U6") (pin "E2") (pinfunction "GND_E2") (pintype "passive"))
      (node (ref "U6") (pin "E3") (pinfunction "GND_E3") (pintype "passive"))
      (node (ref "U6") (pin "E4") (pinfunction "GND_E4") (pintype "passive"))
      (node (ref "U6") (pin "E5") (pinfunction "GND_E5") (pintype "passive"))
      (node (ref "U6") (pin "E6") (pinfunction "GND_E6") (pintype "passive"))
      (node (ref "U6") (pin "E7") (pinfunction "GND_E7") (pintype "passive"))
      (node (ref "U6") (pin "F4") (pinfunction "GND_F4") (pintype "passive"))
      (node (ref "U6") (pin "F5") (pinfunction "GND_F5") (pintype "passive"))
      (node (ref "U6") (pin "F6") (pinfunction "GND_F6") (pintype "passive"))
      (node (ref "U6") (pin "F7") (pinfunction "GND_F7") (pintype "passive"))
      (node (ref "U6") (pin "G4") (pinfunction "GND_G4") (pintype "passive"))
      (node (ref "U6") (pin "G5") (pinfunction "GND_G5") (pintype "passive"))
      (node (ref "U6") (pin "G6") (pinfunction "GND_G6") (pintype "passive"))
      (node (ref "U6") (pin "H4") (pinfunction "GND_H4") (pintype "passive"))
      (node (ref "U6") (pin "H5") (pinfunction "GND_H5") (pintype "passive"))
      (node (ref "U6") (pin "H6") (pinfunction "GND_H6") (pintype "passive"))
      (node (ref "U6") (pin "H7") (pinfunction "GND_H7") (pintype "passive"))
      (node (ref "U7") (pin "E1") (pinfunction "GND_E1") (pintype "passive"))
      (node (ref "U7") (pin "E2") (pinfunction "GND_E2") (pintype "passive"))
      (node (ref "U7") (pin "E3") (pinfunction "GND_E3") (pintype "passive"))
      (node (ref "U7") (pin "E4") (pinfunction "GND_E4") (pintype "passive"))
      (node (ref "U7") (pin "E5") (pinfunction "GND_E5") (pintype "passive"))
      (node (ref "U7") (pin "E6") (pinfunction "GND_E6") (pintype "passive"))
      (node (ref "U7") (pin "E7") (pinfunction "GND_E7") (pintype "passive"))
      (node (ref "U7") (pin "F4") (pinfunction "GND_F4") (pintype "passive"))
      (node (ref "U7") (pin "F5") (pinfunction "GND_F5") (pintype "passive"))
      (node (ref "U7") (pin "F6") (pinfunction "GND_F6") (pintype "passive"))
      (node (ref "U7") (pin "F7") (pinfunction "GND_F7") (pintype "passive"))
      (node (ref "U7") (pin "G4") (pinfunction "GND_G4") (pintype "passive"))
      (node (ref "U7") (pin "G5") (pinfunction "GND_G5") (pintype "passive"))
      (node (ref "U7") (pin "G6") (pinfunction "GND_G6") (pintype "passive"))
      (node (ref "U7") (pin "H4") (pinfunction "GND_H4") (pintype "passive"))
      (node (ref "U7") (pin "H5") (pinfunction "GND_H5") (pintype "passive"))
      (node (ref "U7") (pin "H6") (pinfunction "GND_H6") (pintype "passive"))
      (node (ref "U7") (pin "H7") (pinfunction "GND_H7") (pintype "passive"))
      (node (ref "U8") (pin "A1") (pinfunction "Vout_n_A1") (pintype "passive"))
      (node (ref "U8") (pin "A2") (pinfunction "Vout_n_A2") (pintype "passive"))
      (node (ref "U8") (pin "A3") (pinfunction "Vout_n_A3") (pintype "passive"))
      (node (ref "U8") (pin "A4") (pinfunction "Vout_n_A4") (pintype "passive"))
      (node (ref "U8") (pin "A5") (pinfunction "Vout_n_A5") (pintype "passive"))
      (node (ref "U8") (pin "B1") (pinfunction "Vout_n_B1") (pintype "passive"))
      (node (ref "U8") (pin "B2") (pinfunction "Vout_n_B2") (pintype "passive"))
      (node (ref "U8") (pin "B3") (pinfunction "Vout_n_B3") (pintype "passive"))
      (node (ref "U8") (pin "B4") (pinfunction "Vout_n_B4") (pintype "passive"))
      (node (ref "U8") (pin "B5") (pinfunction "Vout_n_B5") (pintype "passive"))
      (node (ref "U8") (pin "E1") (pinfunction "GND_E1") (pintype "passive"))
      (node (ref "U8") (pin "E2") (pinfunction "GND_E2") (pintype "passive"))
      (node (ref "U8") (pin "E3") (pinfunction "GND_E3") (pintype "passive"))
      (node (ref "U8") (pin "E4") (pinfunction "GND_E4") (pintype "passive"))
      (node (ref "U8") (pin "E5") (pinfunction "GND_E5") (pintype "passive"))
      (node (ref "U8") (pin "E6") (pinfunction "GND_E6") (pintype "passive"))
      (node (ref "U8") (pin "E7") (pinfunction "GND_E7") (pintype "passive"))
      (node (ref "U8") (pin "F4") (pinfunction "GND_F4") (pintype "passive"))
      (node (ref "U8") (pin "F5") (pinfunction "GND_F5") (pintype "passive"))
      (node (ref "U8") (pin "F6") (pinfunction "GND_F6") (pintype "passive"))
      (node (ref "U8") (pin "F7") (pinfunction "GND_F7") (pintype "passive"))
      (node (ref "U8") (pin "G4") (pinfunction "GND_G4") (pintype "passive"))
      (node (ref "U8") (pin "G5") (pinfunction "GND_G5") (pintype "passive"))
      (node (ref "U8") (pin "G6") (pinfunction "GND_G6") (pintype "passive"))
      (node (ref "U8") (pin "H4") (pinfunction "GND_H4") (pintype "passive"))
      (node (ref "U8") (pin "H5") (pinfunction "GND_H5") (pintype "passive"))
      (node (ref "U8") (pin "H6") (pinfunction "GND_H6") (pintype "passive"))
      (node (ref "U8") (pin "H7") (pinfunction "GND_H7") (pintype "passive"))
      (node (ref "U9") (pin "2") (pinfunction "GND_2") (pintype "passive"))
    )
    (net (code "18") (name "Net-(U4-FB)") (class "Default")
      (node (ref "C28") (pin "1") (pintype "passive"))
      (node (ref "R26") (pin "1") (pintype "passive"))
      (node (ref "U4") (pin "G7") (pinfunction "FB_G7") (pintype "passive"))
    )
    (net (code "19") (name "Net-(U5-FB)") (class "Default")
      (node (ref "C29") (pin "1") (pintype "passive"))
      (node (ref "R27") (pin "1") (pintype "passive"))
      (node (ref "U5") (pin "G7") (pinfunction "FB_G7") (pintype "passive"))
    )
    (net (code "20") (name "Net-(U6-FB)") (class "Default")
      (node (ref "C34") (pin "1") (pintype "passive"))
      (node (ref "R28") (pin "1") (pintype "passive"))
      (node (ref "U6") (pin "G7") (pinfunction "FB_G7") (pintype "passive"))
    )
    (net (code "21") (name "Net-(U7-FB)") (class "Default")
      (node (ref "C35") (pin "1") (pintype "passive"))
      (node (ref "R29") (pin "1") (pintype "passive"))
      (node (ref "U7") (pin "G7") (pinfunction "FB_G7") (pintype "passive"))
    )
    (net (code "22") (name "Net-(U8-FB)") (class "Default")
      (node (ref "C41") (pin "1") (pintype "passive"))
      (node (ref "R33") (pin "1") (pintype "passive"))
      (node (ref "U8") (pin "G7") (pinfunction "FB_G7") (pintype "passive"))
    )
    (net (code "23") (name "Net-(U9-MOD)") (class "Default")
      (node (ref "C40") (pin "2") (pintype "passive"))
      (node (ref "U9") (pin "14") (pinfunction "MOD_14") (pintype "passive"))
    )
    (net (code "24") (name "Net-(U9-PH0)") (class "Default")
      (node (ref "R30") (pin "2") (pintype "passive"))
      (node (ref "U9") (pin "3") (pinfunction "PH0_3") (pintype "passive"))
    )
    (net (code "25") (name "Net-(U9-PH1)") (class "Default")
      (node (ref "R31") (pin "2") (pintype "passive"))
      (node (ref "U9") (pin "4") (pinfunction "PH1_4") (pintype "passive"))
    )
    (net (code "26") (name "Net-(U9-SET)") (class "Default")
      (node (ref "R32") (pin "2") (pintype "passive"))
      (node (ref "U9") (pin "16") (pinfunction "SET_16") (pintype "passive"))
    )
    (net (code "27") (name "Vin") (class "Default")
      (node (ref "J1") (pin "1") (pinfunction "1_1") (pintype "passive"))
      (node (ref "J2") (pin "1") (pinfunction "1_1") (pintype "passive"))
    )
    (net (code "28") (name "unconnected-(U9-OUT6-Pad10)") (class "Default")
      (node (ref "U9") (pin "10") (pinfunction "OUT6_10") (pintype "passive+no_connect"))
    )
    (net (code "29") (name "unconnected-(U9-OUT7-Pad11)") (class "Default")
      (node (ref "U9") (pin "11") (pinfunction "OUT7_11") (pintype "passive+no_connect"))
    )
    (net (code "30") (name "unconnected-(U9-OUT8-Pad12)") (class "Default")
      (node (ref "U9") (pin "12") (pinfunction "OUT8_12") (pintype "passive+no_connect"))
    )
  )
)
